# Bee_Snuggler_-_Main.net
KiCad netlist of a schematic drawn in EAGLE
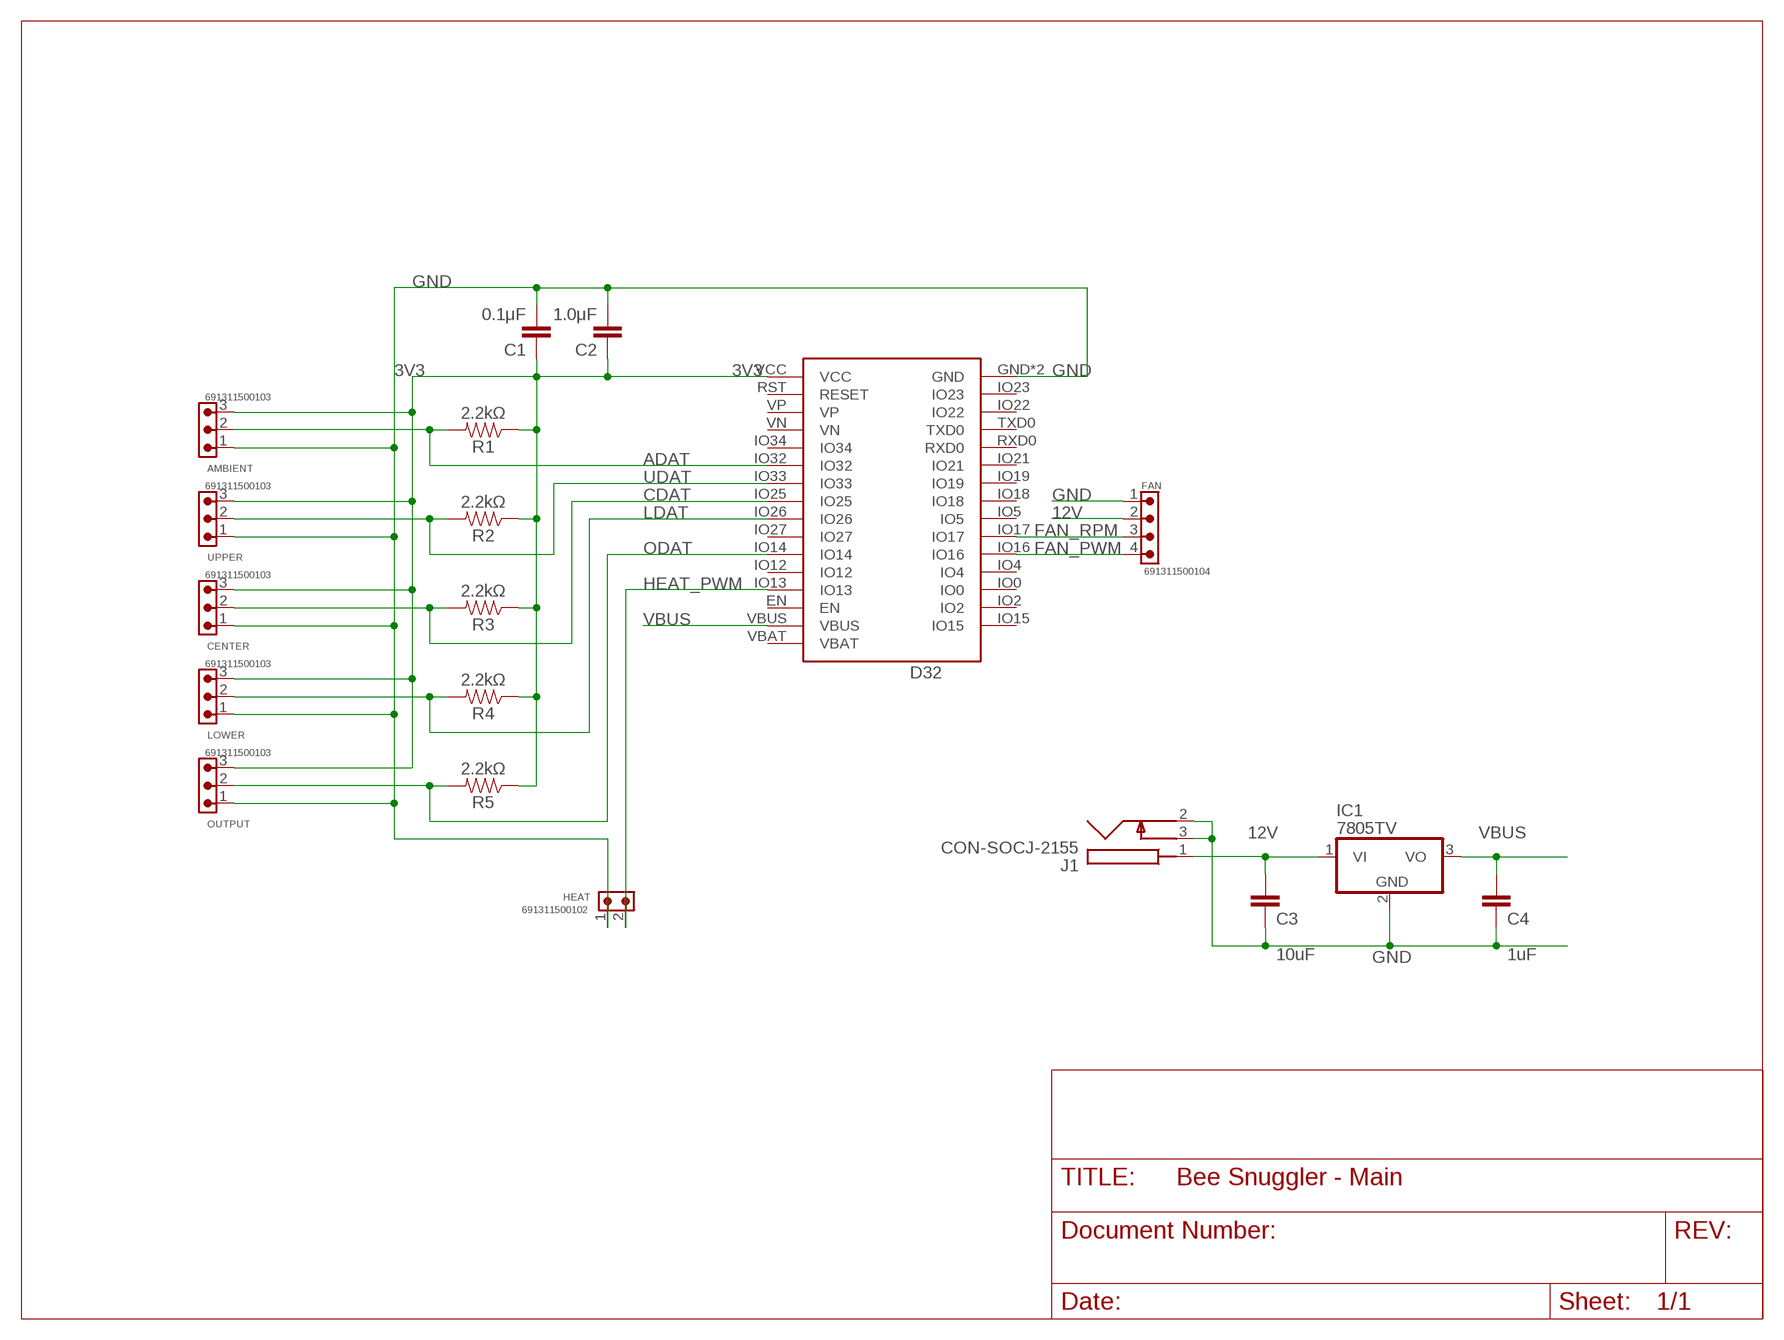
[diagram p0: schematic, sheet 1]

(export (version "E")
  (design (tool "Eeschema 10.0.6"))
  (components
    (comp (ref "AMBIENT")
      (value "691311500103")
      (footprint "eagle-import:691311500103")
      (libsource (lib "eagle-import") (part "691311500103"))
    )
    (comp (ref "C1")
      (value "0.1μF")
      (footprint "eagle-import:CAP_PTH-2.54")
      (libsource (lib "eagle-import") (part "CAP_CERAMIC_2.54"))
    )
    (comp (ref "C2")
      (value "1.0μF")
      (footprint "eagle-import:CAP_PTH-2.54")
      (libsource (lib "eagle-import") (part "CAP_CERAMIC_2.54"))
    )
    (comp (ref "C3")
      (value "10uF")
      (footprint "eagle-import:CAP_PTH-2.54")
      (libsource (lib "eagle-import") (part "CAP_CERAMIC_2.54"))
    )
    (comp (ref "C4")
      (value "1uF")
      (footprint "eagle-import:CAP_PTH-2.54")
      (libsource (lib "eagle-import") (part "CAP_CERAMIC_2.54"))
    )
    (comp (ref "CENTER")
      (value "691311500103")
      (footprint "eagle-import:691311500103")
      (libsource (lib "eagle-import") (part "691311500103"))
    )
    (comp (ref "D32")
      (value "Lolin D32")
      (footprint "eagle-import:D32_PRO")
      (libsource (lib "eagle-import") (part "WEMOS-D32D32_PRO"))
    )
    (comp (ref "FAN")
      (value "691311500104")
      (footprint "eagle-import:691311500104")
      (libsource (lib "eagle-import") (part "691311500104"))
    )
    (comp (ref "HEAT")
      (value "691311500102")
      (footprint "eagle-import:691311500102")
      (libsource (lib "eagle-import") (part "691311500102"))
    )
    (comp (ref "IC1")
      (value "7805TV")
      (footprint "eagle-import:TO220V")
      (libsource (lib "eagle-import") (part "78TV05"))
    )
    (comp (ref "J1")
      (value "CON-SOCJ-2155")
      (footprint "eagle-import:CONSOCJ2155")
      (fields (field (name "MOUSER_PART_NUMBER") "992-CON-SOCJ-2155"))
      (libsource (lib "eagle-import") (part "CON-SOCJ-2155"))
    )
    (comp (ref "LOWER")
      (value "691311500103")
      (footprint "eagle-import:691311500103")
      (libsource (lib "eagle-import") (part "691311500103"))
    )
    (comp (ref "OUTPUT")
      (value "691311500103")
      (footprint "eagle-import:691311500103")
      (libsource (lib "eagle-import") (part "691311500103"))
    )
    (comp (ref "R1")
      (value "2.2kΩ")
      (footprint "eagle-import:AXIAL-0.3")
      (libsource (lib "eagle-import") (part "RESISTORAXIAL-0.3"))
    )
    (comp (ref "R2")
      (value "2.2kΩ")
      (footprint "eagle-import:AXIAL-0.3")
      (libsource (lib "eagle-import") (part "RESISTORAXIAL-0.3"))
    )
    (comp (ref "R3")
      (value "2.2kΩ")
      (footprint "eagle-import:AXIAL-0.3")
      (libsource (lib "eagle-import") (part "RESISTORAXIAL-0.3"))
    )
    (comp (ref "R4")
      (value "2.2kΩ")
      (footprint "eagle-import:AXIAL-0.3")
      (libsource (lib "eagle-import") (part "RESISTORAXIAL-0.3"))
    )
    (comp (ref "R5")
      (value "2.2kΩ")
      (footprint "eagle-import:AXIAL-0.3")
      (libsource (lib "eagle-import") (part "RESISTORAXIAL-0.3"))
    )
    (comp (ref "UPPER")
      (value "691311500103")
      (footprint "eagle-import:691311500103")
      (libsource (lib "eagle-import") (part "691311500103"))
    )
  )
  (nets
    (net (code "1") (name "/3V3") (class "Default")
      (node (ref "AMBIENT") (pin "3") (pinfunction "3_3") (pintype "passive"))
      (node (ref "C1") (pin "1") (pinfunction "1_1") (pintype "passive"))
      (node (ref "C2") (pin "1") (pinfunction "1_1") (pintype "passive"))
      (node (ref "CENTER") (pin "3") (pinfunction "3_3") (pintype "passive"))
      (node (ref "D32") (pin "VCC") (pinfunction "VCC_VCC") (pintype "power_in"))
      (node (ref "LOWER") (pin "3") (pinfunction "3_3") (pintype "passive"))
      (node (ref "OUTPUT") (pin "3") (pinfunction "3_3") (pintype "passive"))
      (node (ref "R1") (pin "P$1") (pinfunction "1_P$1") (pintype "passive"))
      (node (ref "R2") (pin "P$1") (pinfunction "1_P$1") (pintype "passive"))
      (node (ref "R3") (pin "P$1") (pinfunction "1_P$1") (pintype "passive"))
      (node (ref "R4") (pin "P$1") (pinfunction "1_P$1") (pintype "passive"))
      (node (ref "R5") (pin "P$1") (pinfunction "1_P$1") (pintype "passive"))
      (node (ref "UPPER") (pin "3") (pinfunction "3_3") (pintype "passive"))
    )
    (net (code "2") (name "/12V") (class "Default")
      (node (ref "C3") (pin "1") (pinfunction "1_1") (pintype "passive"))
      (node (ref "FAN") (pin "2") (pinfunction "2_2") (pintype "passive"))
      (node (ref "IC1") (pin "1") (pinfunction "VI_1") (pintype "input"))
      (node (ref "J1") (pin "1") (pinfunction "1_1") (pintype "bidirectional"))
    )
    (net (code "3") (name "/ADAT") (class "Default")
      (node (ref "AMBIENT") (pin "2") (pinfunction "2_2") (pintype "passive"))
      (node (ref "D32") (pin "IO32") (pinfunction "IO32_IO32") (pintype "bidirectional"))
      (node (ref "R1") (pin "P$2") (pinfunction "2_P$2") (pintype "passive"))
    )
    (net (code "4") (name "/CDAT") (class "Default")
      (node (ref "CENTER") (pin "2") (pinfunction "2_2") (pintype "passive"))
      (node (ref "D32") (pin "IO25") (pinfunction "IO25_IO25") (pintype "bidirectional"))
      (node (ref "R3") (pin "P$2") (pinfunction "2_P$2") (pintype "passive"))
    )
    (net (code "5") (name "/FAN_PWM") (class "Default")
      (node (ref "D32") (pin "IO16") (pinfunction "IO16_IO16") (pintype "bidirectional"))
      (node (ref "FAN") (pin "4") (pinfunction "4_4") (pintype "passive"))
    )
    (net (code "6") (name "/FAN_RPM") (class "Default")
      (node (ref "D32") (pin "IO17") (pinfunction "IO17_IO17") (pintype "bidirectional"))
      (node (ref "FAN") (pin "3") (pinfunction "3_3") (pintype "passive"))
    )
    (net (code "7") (name "/GND") (class "Default")
      (node (ref "AMBIENT") (pin "1") (pinfunction "1_1") (pintype "passive"))
      (node (ref "C1") (pin "2") (pinfunction "2_2") (pintype "passive"))
      (node (ref "C2") (pin "2") (pinfunction "2_2") (pintype "passive"))
      (node (ref "C3") (pin "2") (pinfunction "2_2") (pintype "passive"))
      (node (ref "C4") (pin "2") (pinfunction "2_2") (pintype "passive"))
      (node (ref "CENTER") (pin "1") (pinfunction "1_1") (pintype "passive"))
      (node (ref "D32") (pin "GND") (pinfunction "GND_GND") (pintype "power_in"))
      (node (ref "D32") (pin "GND2") (pinfunction "GND_GND2") (pintype "power_in"))
      (node (ref "FAN") (pin "1") (pinfunction "1_1") (pintype "passive"))
      (node (ref "HEAT") (pin "1") (pinfunction "1_1") (pintype "passive"))
      (node (ref "IC1") (pin "2") (pinfunction "GND_2") (pintype "passive"))
      (node (ref "J1") (pin "2") (pinfunction "2_2") (pintype "bidirectional"))
      (node (ref "J1") (pin "3") (pinfunction "3_3") (pintype "bidirectional"))
      (node (ref "LOWER") (pin "1") (pinfunction "1_1") (pintype "passive"))
      (node (ref "OUTPUT") (pin "1") (pinfunction "1_1") (pintype "passive"))
      (node (ref "UPPER") (pin "1") (pinfunction "1_1") (pintype "passive"))
    )
    (net (code "8") (name "/HEAT_PWM") (class "Default")
      (node (ref "D32") (pin "IO13") (pinfunction "IO13_IO13") (pintype "bidirectional"))
      (node (ref "HEAT") (pin "2") (pinfunction "2_2") (pintype "passive"))
    )
    (net (code "9") (name "/LDAT") (class "Default")
      (node (ref "D32") (pin "IO26") (pinfunction "IO26_IO26") (pintype "bidirectional"))
      (node (ref "LOWER") (pin "2") (pinfunction "2_2") (pintype "passive"))
      (node (ref "R4") (pin "P$2") (pinfunction "2_P$2") (pintype "passive"))
    )
    (net (code "10") (name "/ODAT") (class "Default")
      (node (ref "D32") (pin "IO14") (pinfunction "IO14_IO14") (pintype "bidirectional"))
      (node (ref "OUTPUT") (pin "2") (pinfunction "2_2") (pintype "passive"))
      (node (ref "R5") (pin "P$2") (pinfunction "2_P$2") (pintype "passive"))
    )
    (net (code "11") (name "/UDAT") (class "Default")
      (node (ref "D32") (pin "IO33") (pinfunction "IO33_IO33") (pintype "bidirectional"))
      (node (ref "R2") (pin "P$2") (pinfunction "2_P$2") (pintype "passive"))
      (node (ref "UPPER") (pin "2") (pinfunction "2_2") (pintype "passive"))
    )
    (net (code "12") (name "/VBUS") (class "Default")
      (node (ref "C4") (pin "1") (pinfunction "1_1") (pintype "passive"))
      (node (ref "D32") (pin "VBUS") (pinfunction "VBUS_VBUS") (pintype "bidirectional"))
      (node (ref "IC1") (pin "3") (pinfunction "VO_3") (pintype "passive"))
    )
    (net (code "13") (name "unconnected-(D32-PadEN)") (class "Default")
      (node (ref "D32") (pin "EN") (pinfunction "EN_EN") (pintype "bidirectional"))
    )
    (net (code "14") (name "unconnected-(D32-PadIO0)") (class "Default")
      (node (ref "D32") (pin "IO0") (pinfunction "IO0_IO0") (pintype "bidirectional"))
    )
    (net (code "15") (name "unconnected-(D32-PadIO2)") (class "Default")
      (node (ref "D32") (pin "IO2") (pinfunction "IO2_IO2") (pintype "bidirectional"))
    )
    (net (code "16") (name "unconnected-(D32-PadIO4)") (class "Default")
      (node (ref "D32") (pin "IO4") (pinfunction "IO4_IO4") (pintype "bidirectional"))
    )
    (net (code "17") (name "unconnected-(D32-PadIO5)") (class "Default")
      (node (ref "D32") (pin "IO5") (pinfunction "IO5_IO5") (pintype "bidirectional"))
    )
    (net (code "18") (name "unconnected-(D32-PadIO12)") (class "Default")
      (node (ref "D32") (pin "IO12") (pinfunction "IO12_IO12") (pintype "bidirectional"))
    )
    (net (code "19") (name "unconnected-(D32-PadIO15)") (class "Default")
      (node (ref "D32") (pin "IO15") (pinfunction "IO15_IO15") (pintype "bidirectional"))
    )
    (net (code "20") (name "unconnected-(D32-PadIO18)") (class "Default")
      (node (ref "D32") (pin "IO18") (pinfunction "IO18_IO18") (pintype "bidirectional"))
    )
    (net (code "21") (name "unconnected-(D32-PadIO19)") (class "Default")
      (node (ref "D32") (pin "IO19") (pinfunction "IO19_IO19") (pintype "bidirectional"))
    )
    (net (code "22") (name "unconnected-(D32-PadIO21)") (class "Default")
      (node (ref "D32") (pin "IO21") (pinfunction "IO21_IO21") (pintype "bidirectional"))
    )
    (net (code "23") (name "unconnected-(D32-PadIO22)") (class "Default")
      (node (ref "D32") (pin "IO22") (pinfunction "IO22_IO22") (pintype "bidirectional"))
    )
    (net (code "24") (name "unconnected-(D32-PadIO23)") (class "Default")
      (node (ref "D32") (pin "IO23") (pinfunction "IO23_IO23") (pintype "bidirectional"))
    )
    (net (code "25") (name "unconnected-(D32-PadIO27)") (class "Default")
      (node (ref "D32") (pin "IO27") (pinfunction "IO27_IO27") (pintype "bidirectional"))
    )
    (net (code "26") (name "unconnected-(D32-PadIO34)") (class "Default")
      (node (ref "D32") (pin "IO34") (pinfunction "IO34_IO34") (pintype "bidirectional"))
    )
    (net (code "27") (name "unconnected-(D32-PadRXD0)") (class "Default")
      (node (ref "D32") (pin "RXD0") (pinfunction "RXD0_RXD0") (pintype "input"))
    )
    (net (code "28") (name "unconnected-(D32-PadTXD0)") (class "Default")
      (node (ref "D32") (pin "TXD0") (pinfunction "TXD0_TXD0") (pintype "output"))
    )
    (net (code "29") (name "unconnected-(D32-PadVBAT)") (class "Default")
      (node (ref "D32") (pin "VBAT") (pinfunction "VBAT_VBAT") (pintype "bidirectional"))
    )
    (net (code "30") (name "unconnected-(D32-PadVN)") (class "Default")
      (node (ref "D32") (pin "VN") (pinfunction "VN_VN") (pintype "bidirectional"))
    )
    (net (code "31") (name "unconnected-(D32-PadVP)") (class "Default")
      (node (ref "D32") (pin "VP") (pinfunction "VP_VP") (pintype "bidirectional"))
    )
    (net (code "32") (name "unconnected-(D32-RESET-PadRST)") (class "Default")
      (node (ref "D32") (pin "RST") (pinfunction "RESET_RST") (pintype "bidirectional"))
    )
  )
)
